# receiver_shield.net
KiCad netlist of a schematic drawn in EAGLE
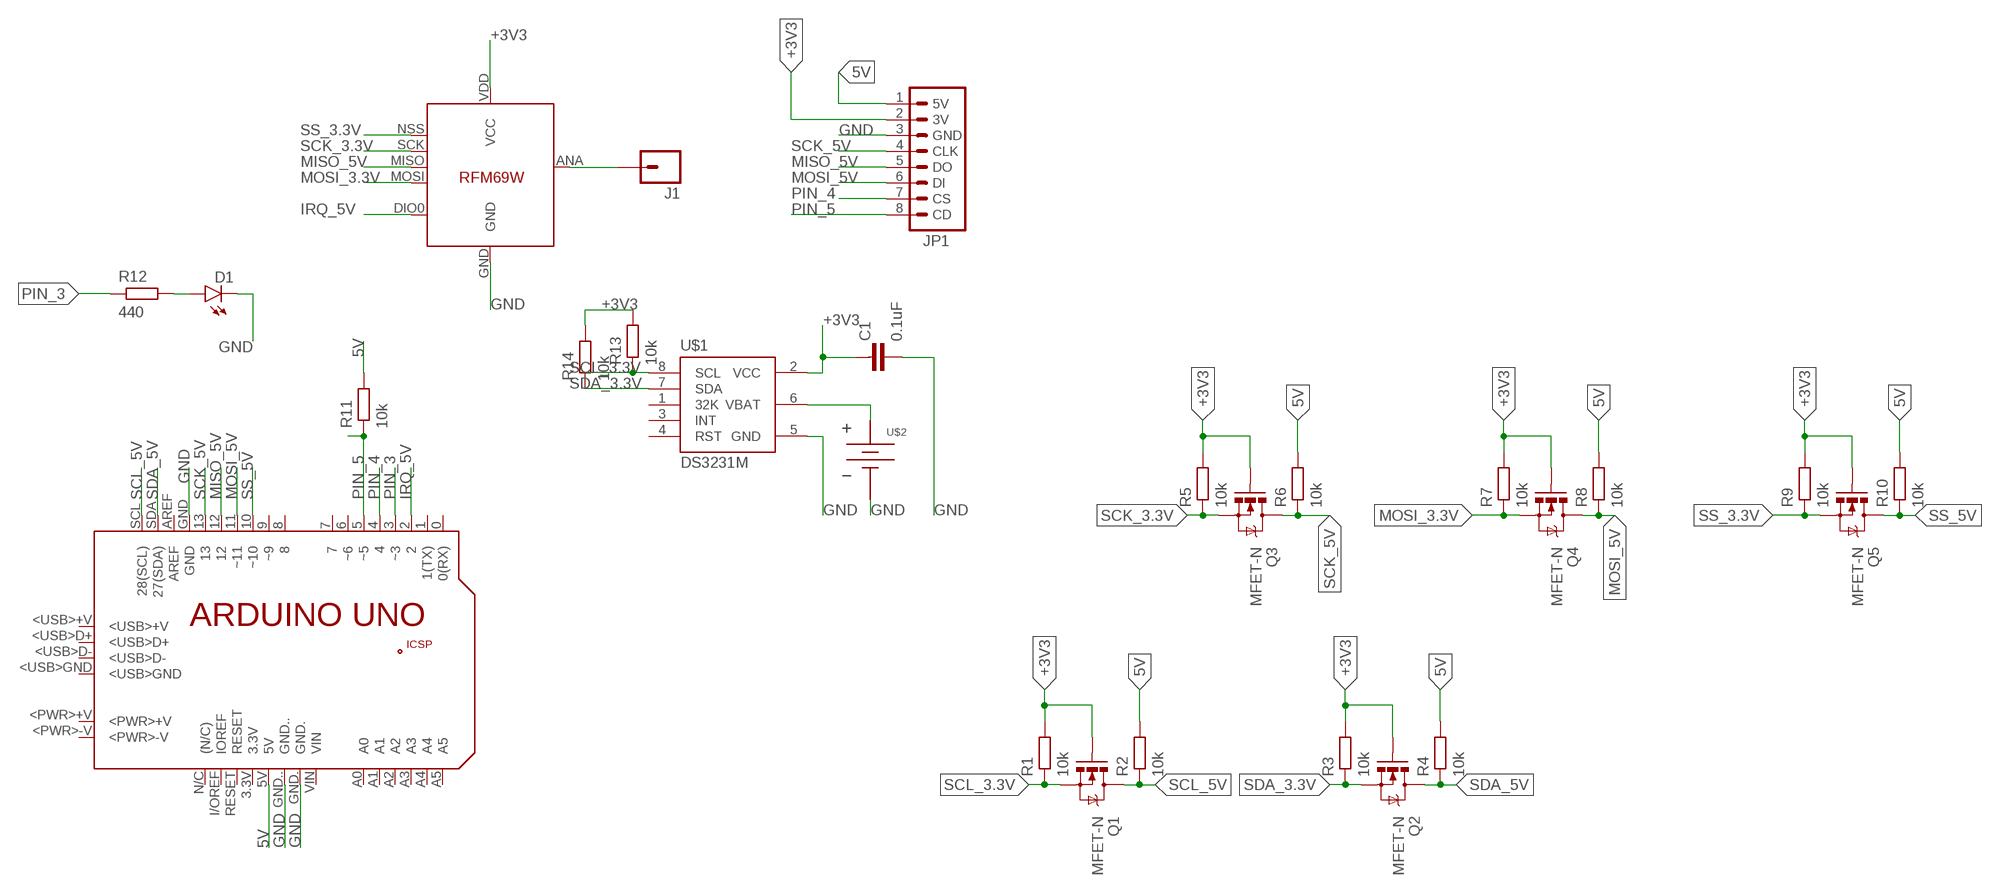
[diagram p0: schematic, sheet 1]

(export (version "E")
  (design (tool "Eeschema 10.0.6"))
  (components
    (comp (ref "C1")
      (value "0.1uF")
      (footprint "eagle-import:C0603-N")
      (libsource (lib "eagle-import") (part "CAPACITOR0603-N"))
    )
    (comp (ref "D1")
      (value "LED0603")
      (footprint "eagle-import:LED-0603")
      (libsource (lib "eagle-import") (part "LED0603"))
    )
    (comp (ref "J1")
      (value "M01NOSILK-KIT")
      (footprint "eagle-import:1X01NS-KIT")
      (libsource (lib "eagle-import") (part "M01NOSILK-KIT"))
    )
    (comp (ref "JP1")
      (value "SDCARD_BREAKOUT_HEADER1X08")
      (footprint "eagle-import:SD_HEADER")
      (libsource (lib "eagle-import") (part "SDCARD_BREAKOUT_HEADER1X08"))
    )
    (comp (ref "PCB1")
      (value "ARDUINO_UNO")
      (footprint "eagle-import:ARDUINO_UNO")
      (libsource (lib "eagle-import") (part "ARDUINO_UNO"))
    )
    (comp (ref "Q1")
      (value "MFET-N")
      (footprint "eagle-import:SOT23-3")
      (libsource (lib "eagle-import") (part "MOSFET-NCHANNELAO3404A"))
    )
    (comp (ref "Q2")
      (value "MFET-N")
      (footprint "eagle-import:SOT23-3")
      (libsource (lib "eagle-import") (part "MOSFET-NCHANNELAO3404A"))
    )
    (comp (ref "Q3")
      (value "MFET-N")
      (footprint "eagle-import:SOT23-3")
      (libsource (lib "eagle-import") (part "MOSFET-NCHANNELAO3404A"))
    )
    (comp (ref "Q4")
      (value "MFET-N")
      (footprint "eagle-import:SOT23-3")
      (libsource (lib "eagle-import") (part "MOSFET-NCHANNELAO3404A"))
    )
    (comp (ref "Q5")
      (value "MFET-N")
      (footprint "eagle-import:SOT23-3")
      (libsource (lib "eagle-import") (part "MOSFET-NCHANNELAO3404A"))
    )
    (comp (ref "R1")
      (value "10k")
      (footprint "eagle-import:R0603-N")
      (libsource (lib "eagle-import") (part "RESISTOR0603-N"))
    )
    (comp (ref "R2")
      (value "10k")
      (footprint "eagle-import:R0603-N")
      (libsource (lib "eagle-import") (part "RESISTOR0603-N"))
    )
    (comp (ref "R3")
      (value "10k")
      (footprint "eagle-import:R0603-N")
      (libsource (lib "eagle-import") (part "RESISTOR0603-N"))
    )
    (comp (ref "R4")
      (value "10k")
      (footprint "eagle-import:R0603-N")
      (libsource (lib "eagle-import") (part "RESISTOR0603-N"))
    )
    (comp (ref "R5")
      (value "10k")
      (footprint "eagle-import:R0603-N")
      (libsource (lib "eagle-import") (part "RESISTOR0603-N"))
    )
    (comp (ref "R6")
      (value "10k")
      (footprint "eagle-import:R0603-N")
      (libsource (lib "eagle-import") (part "RESISTOR0603-N"))
    )
    (comp (ref "R7")
      (value "10k")
      (footprint "eagle-import:R0603-N")
      (libsource (lib "eagle-import") (part "RESISTOR0603-N"))
    )
    (comp (ref "R8")
      (value "10k")
      (footprint "eagle-import:R0603-N")
      (libsource (lib "eagle-import") (part "RESISTOR0603-N"))
    )
    (comp (ref "R9")
      (value "10k")
      (footprint "eagle-import:R0603-N")
      (libsource (lib "eagle-import") (part "RESISTOR0603-N"))
    )
    (comp (ref "R10")
      (value "10k")
      (footprint "eagle-import:R0603-N")
      (libsource (lib "eagle-import") (part "RESISTOR0603-N"))
    )
    (comp (ref "R11")
      (value "10k")
      (footprint "eagle-import:R0603-N")
      (libsource (lib "eagle-import") (part "RESISTOR0603-N"))
    )
    (comp (ref "R12")
      (value "440")
      (footprint "eagle-import:R0603-N")
      (libsource (lib "eagle-import") (part "RESISTOR0603-N"))
    )
    (comp (ref "R13")
      (value "10k")
      (footprint "eagle-import:R0603-N")
      (libsource (lib "eagle-import") (part "RESISTOR0603-N"))
    )
    (comp (ref "R14")
      (value "10k")
      (footprint "eagle-import:R0603-N")
      (libsource (lib "eagle-import") (part "RESISTOR0603-N"))
    )
    (comp (ref "U$1")
      (value "DS3231M")
      (footprint "eagle-import:SO08")
      (libsource (lib "eagle-import") (part "DS3231M"))
    )
    (comp (ref "U$2")
      (value "2032_BAT_HLDR")
      (footprint "eagle-import:2032_BAT_HLDR_MPD")
      (libsource (lib "eagle-import") (part "2032_BAT_HLDR"))
    )
    (comp (ref "U$4")
      (value "RFM69")
      (footprint "eagle-import:RFM69W-MINPADS")
      (libsource (lib "eagle-import") (part "RFM69"))
    )
  )
  (nets
    (net (code "1") (name "+3V3") (class "Default")
      (node (ref "C1") (pin "1") (pinfunction "1_1") (pintype "passive"))
      (node (ref "JP1") (pin "2") (pinfunction "3V_2") (pintype "passive"))
      (node (ref "Q1") (pin "1") (pinfunction "G_1") (pintype "passive"))
      (node (ref "Q2") (pin "1") (pinfunction "G_1") (pintype "passive"))
      (node (ref "Q3") (pin "1") (pinfunction "G_1") (pintype "passive"))
      (node (ref "Q4") (pin "1") (pinfunction "G_1") (pintype "passive"))
      (node (ref "Q5") (pin "1") (pinfunction "G_1") (pintype "passive"))
      (node (ref "R1") (pin "2") (pinfunction "P$2_2") (pintype "passive"))
      (node (ref "R13") (pin "2") (pinfunction "P$2_2") (pintype "passive"))
      (node (ref "R14") (pin "2") (pinfunction "P$2_2") (pintype "passive"))
      (node (ref "R3") (pin "2") (pinfunction "P$2_2") (pintype "passive"))
      (node (ref "R5") (pin "2") (pinfunction "P$2_2") (pintype "passive"))
      (node (ref "R7") (pin "2") (pinfunction "P$2_2") (pintype "passive"))
      (node (ref "R9") (pin "2") (pinfunction "P$2_2") (pintype "passive"))
      (node (ref "U$1") (pin "2") (pinfunction "VCC_2") (pintype "power_in"))
      (node (ref "U$4") (pin "VDD") (pinfunction "VCC_VDD") (pintype "power_in"))
    )
    (net (code "2") (name "/GND") (class "Default")
      (node (ref "C1") (pin "2") (pinfunction "2_2") (pintype "passive"))
      (node (ref "D1") (pin "C") (pinfunction "C_C") (pintype "passive"))
      (node (ref "JP1") (pin "3") (pinfunction "GND_3") (pintype "passive"))
      (node (ref "PCB1") (pin "GND") (pinfunction "GND_GND") (pintype "bidirectional"))
      (node (ref "PCB1") (pin "GND.") (pinfunction "GND._GND.") (pintype "bidirectional"))
      (node (ref "PCB1") (pin "GND..") (pinfunction "GND.._GND..") (pintype "bidirectional"))
      (node (ref "U$1") (pin "5") (pinfunction "GND_5") (pintype "power_in"))
      (node (ref "U$2") (pin "P$1") (pinfunction "GND_P$1") (pintype "bidirectional"))
      (node (ref "U$4") (pin "GND") (pinfunction "GND_GND") (pintype "power_in"))
    )
    (net (code "3") (name "/IRQ_5V") (class "Default")
      (node (ref "PCB1") (pin "2") (pinfunction "2_2") (pintype "bidirectional"))
      (node (ref "U$4") (pin "DIO0") (pinfunction "DIO0_DIO0") (pintype "open_collector"))
    )
    (net (code "4") (name "/MISO_5V") (class "Default")
      (node (ref "JP1") (pin "5") (pinfunction "DO_5") (pintype "passive"))
      (node (ref "PCB1") (pin "12") (pinfunction "12_12") (pintype "bidirectional"))
      (node (ref "U$4") (pin "MISO") (pinfunction "MISO_MISO") (pintype "input"))
    )
    (net (code "5") (name "/PIN_4") (class "Default")
      (node (ref "JP1") (pin "7") (pinfunction "CS_7") (pintype "passive"))
      (node (ref "PCB1") (pin "4") (pinfunction "4_4") (pintype "bidirectional"))
    )
    (net (code "6") (name "/PIN_5") (class "Default")
      (node (ref "JP1") (pin "8") (pinfunction "CD_8") (pintype "passive"))
      (node (ref "PCB1") (pin "5") (pinfunction "~{5}_5") (pintype "bidirectional"))
      (node (ref "R11") (pin "1") (pinfunction "P$1_1") (pintype "passive"))
    )
    (net (code "7") (name "5V") (class "Default")
      (node (ref "JP1") (pin "1") (pinfunction "5V_1") (pintype "passive"))
      (node (ref "PCB1") (pin "5V") (pinfunction "5V_5V") (pintype "bidirectional"))
      (node (ref "R10") (pin "2") (pinfunction "P$2_2") (pintype "passive"))
      (node (ref "R11") (pin "2") (pinfunction "P$2_2") (pintype "passive"))
      (node (ref "R2") (pin "2") (pinfunction "P$2_2") (pintype "passive"))
      (node (ref "R4") (pin "2") (pinfunction "P$2_2") (pintype "passive"))
      (node (ref "R6") (pin "2") (pinfunction "P$2_2") (pintype "passive"))
      (node (ref "R8") (pin "2") (pinfunction "P$2_2") (pintype "passive"))
    )
    (net (code "8") (name "MOSI_3.3V") (class "Default")
      (node (ref "Q4") (pin "2") (pinfunction "S_2") (pintype "passive"))
      (node (ref "R7") (pin "1") (pinfunction "P$1_1") (pintype "passive"))
      (node (ref "U$4") (pin "MOSI") (pinfunction "MOSI_MOSI") (pintype "output"))
    )
    (net (code "9") (name "MOSI_5V") (class "Default")
      (node (ref "JP1") (pin "6") (pinfunction "DI_6") (pintype "passive"))
      (node (ref "PCB1") (pin "11") (pinfunction "~{11}_11") (pintype "bidirectional"))
      (node (ref "Q4") (pin "3") (pinfunction "D_3") (pintype "passive"))
      (node (ref "R8") (pin "1") (pinfunction "P$1_1") (pintype "passive"))
    )
    (net (code "10") (name "Net-(R12-P$2)") (class "Default")
      (node (ref "D1") (pin "A") (pinfunction "A_A") (pintype "passive"))
      (node (ref "R12") (pin "2") (pinfunction "P$2_2") (pintype "passive"))
    )
    (net (code "11") (name "Net-(U$1-VBAT)") (class "Default")
      (node (ref "U$1") (pin "6") (pinfunction "VBAT_6") (pintype "power_in"))
      (node (ref "U$2") (pin "P$2") (pinfunction "VBAT_P$2") (pintype "bidirectional"))
    )
    (net (code "12") (name "Net-(U$4-ANT)") (class "Default")
      (node (ref "J1") (pin "1") (pinfunction "1_1") (pintype "passive"))
      (node (ref "U$4") (pin "ANA") (pinfunction "ANT_ANA") (pintype "passive"))
    )
    (net (code "13") (name "PIN_3") (class "Default")
      (node (ref "PCB1") (pin "3") (pinfunction "~{3}_3") (pintype "bidirectional"))
      (node (ref "R12") (pin "1") (pinfunction "P$1_1") (pintype "passive"))
    )
    (net (code "14") (name "SCK_3.3V") (class "Default")
      (node (ref "Q3") (pin "2") (pinfunction "S_2") (pintype "passive"))
      (node (ref "R5") (pin "1") (pinfunction "P$1_1") (pintype "passive"))
      (node (ref "U$4") (pin "SCK") (pinfunction "SCK_SCK") (pintype "input"))
    )
    (net (code "15") (name "SCK_5V") (class "Default")
      (node (ref "JP1") (pin "4") (pinfunction "CLK_4") (pintype "passive"))
      (node (ref "PCB1") (pin "13") (pinfunction "13_13") (pintype "bidirectional"))
      (node (ref "Q3") (pin "3") (pinfunction "D_3") (pintype "passive"))
      (node (ref "R6") (pin "1") (pinfunction "P$1_1") (pintype "passive"))
    )
    (net (code "16") (name "SCL_3.3V") (class "Default")
      (node (ref "Q1") (pin "2") (pinfunction "S_2") (pintype "passive"))
      (node (ref "R1") (pin "1") (pinfunction "P$1_1") (pintype "passive"))
      (node (ref "R13") (pin "1") (pinfunction "P$1_1") (pintype "passive"))
      (node (ref "U$1") (pin "8") (pinfunction "SCL_8") (pintype "bidirectional"))
    )
    (net (code "17") (name "SCL_5V") (class "Default")
      (node (ref "PCB1") (pin "SCL") (pinfunction "28(SCL)_SCL") (pintype "bidirectional"))
      (node (ref "Q1") (pin "3") (pinfunction "D_3") (pintype "passive"))
      (node (ref "R2") (pin "1") (pinfunction "P$1_1") (pintype "passive"))
    )
    (net (code "18") (name "SDA_3.3V") (class "Default")
      (node (ref "Q2") (pin "2") (pinfunction "S_2") (pintype "passive"))
      (node (ref "R14") (pin "1") (pinfunction "P$1_1") (pintype "passive"))
      (node (ref "R3") (pin "1") (pinfunction "P$1_1") (pintype "passive"))
      (node (ref "U$1") (pin "7") (pinfunction "SDA_7") (pintype "bidirectional"))
    )
    (net (code "19") (name "SDA_5V") (class "Default")
      (node (ref "PCB1") (pin "SDA") (pinfunction "27(SDA)_SDA") (pintype "bidirectional"))
      (node (ref "Q2") (pin "3") (pinfunction "D_3") (pintype "passive"))
      (node (ref "R4") (pin "1") (pinfunction "P$1_1") (pintype "passive"))
    )
    (net (code "20") (name "SS_3.3V") (class "Default")
      (node (ref "Q5") (pin "2") (pinfunction "S_2") (pintype "passive"))
      (node (ref "R9") (pin "1") (pinfunction "P$1_1") (pintype "passive"))
      (node (ref "U$4") (pin "NSS") (pinfunction "SEL_NSS") (pintype "input"))
    )
    (net (code "21") (name "SS_5V") (class "Default")
      (node (ref "PCB1") (pin "10") (pinfunction "~{10}_10") (pintype "bidirectional"))
      (node (ref "Q5") (pin "3") (pinfunction "D_3") (pintype "passive"))
      (node (ref "R10") (pin "1") (pinfunction "P$1_1") (pintype "passive"))
    )
    (net (code "22") (name "unconnected-(PCB1-(N{slash}C)-PadN{slash}C)") (class "Default")
      (node (ref "PCB1") (pin "N/C") (pinfunction "(N/C)_N/C") (pintype "bidirectional"))
    )
    (net (code "23") (name "unconnected-(PCB1-0(RX)-Pad0)") (class "Default")
      (node (ref "PCB1") (pin "0") (pinfunction "0(RX)_0") (pintype "bidirectional"))
    )
    (net (code "24") (name "unconnected-(PCB1-1(TX)-Pad1)") (class "Default")
      (node (ref "PCB1") (pin "1") (pinfunction "1(TX)_1") (pintype "bidirectional"))
    )
    (net (code "25") (name "unconnected-(PCB1-IOREF-PadI{slash}OREF)") (class "Default")
      (node (ref "PCB1") (pin "I/OREF") (pinfunction "IOREF_I/OREF") (pintype "bidirectional"))
    )
    (net (code "26") (name "unconnected-(PCB1-Pad+5V)") (class "Default")
      (node (ref "PCB1") (pin "+5V") (pinfunction "+5V_+5V") (pintype "bidirectional"))
    )
    (net (code "27") (name "unconnected-(PCB1-Pad3.3V)") (class "Default")
      (node (ref "PCB1") (pin "3.3V") (pinfunction "3.3V_3.3V") (pintype "bidirectional"))
    )
    (net (code "28") (name "unconnected-(PCB1-Pad7)") (class "Default")
      (node (ref "PCB1") (pin "7") (pinfunction "7_7") (pintype "bidirectional"))
    )
    (net (code "29") (name "unconnected-(PCB1-Pad8)") (class "Default")
      (node (ref "PCB1") (pin "8") (pinfunction "8_8") (pintype "bidirectional"))
    )
    (net (code "30") (name "unconnected-(PCB1-Pad<PWR>+V)") (class "Default")
      (node (ref "PCB1") (pin "<PWR>+V") (pinfunction "<PWR>+V_<PWR>+V") (pintype "bidirectional"))
    )
    (net (code "31") (name "unconnected-(PCB1-Pad<PWR>-V)") (class "Default")
      (node (ref "PCB1") (pin "<PWR>-V") (pinfunction "<PWR>-V_<PWR>-V") (pintype "bidirectional"))
    )
    (net (code "32") (name "unconnected-(PCB1-Pad<USB>+V)") (class "Default")
      (node (ref "PCB1") (pin "<USB>+V") (pinfunction "<USB>+V_<USB>+V") (pintype "bidirectional"))
    )
    (net (code "33") (name "unconnected-(PCB1-Pad<USB>D+)") (class "Default")
      (node (ref "PCB1") (pin "<USB>D+") (pinfunction "<USB>D+_<USB>D+") (pintype "bidirectional"))
    )
    (net (code "34") (name "unconnected-(PCB1-Pad<USB>D-)") (class "Default")
      (node (ref "PCB1") (pin "<USB>D-") (pinfunction "<USB>D-_<USB>D-") (pintype "bidirectional"))
    )
    (net (code "35") (name "unconnected-(PCB1-Pad<USB>GND)") (class "Default")
      (node (ref "PCB1") (pin "<USB>GND") (pinfunction "<USB>GND_<USB>GND") (pintype "bidirectional"))
    )
    (net (code "36") (name "unconnected-(PCB1-PadA0)") (class "Default")
      (node (ref "PCB1") (pin "A0") (pinfunction "A0_A0") (pintype "bidirectional"))
    )
    (net (code "37") (name "unconnected-(PCB1-PadA1)") (class "Default")
      (node (ref "PCB1") (pin "A1") (pinfunction "A1_A1") (pintype "bidirectional"))
    )
    (net (code "38") (name "unconnected-(PCB1-PadA2)") (class "Default")
      (node (ref "PCB1") (pin "A2") (pinfunction "A2_A2") (pintype "bidirectional"))
    )
    (net (code "39") (name "unconnected-(PCB1-PadA3)") (class "Default")
      (node (ref "PCB1") (pin "A3") (pinfunction "A3_A3") (pintype "bidirectional"))
    )
    (net (code "40") (name "unconnected-(PCB1-PadA4)") (class "Default")
      (node (ref "PCB1") (pin "A4") (pinfunction "A4_A4") (pintype "bidirectional"))
    )
    (net (code "41") (name "unconnected-(PCB1-PadA5)") (class "Default")
      (node (ref "PCB1") (pin "A5") (pinfunction "A5_A5") (pintype "bidirectional"))
    )
    (net (code "42") (name "unconnected-(PCB1-PadAREF)") (class "Default")
      (node (ref "PCB1") (pin "AREF") (pinfunction "AREF_AREF") (pintype "bidirectional"))
    )
    (net (code "43") (name "unconnected-(PCB1-PadGND_)") (class "Default")
      (node (ref "PCB1") (pin "GND_") (pinfunction "GND__GND_") (pintype "bidirectional"))
    )
    (net (code "44") (name "unconnected-(PCB1-PadMISO)") (class "Default")
      (node (ref "PCB1") (pin "MISO") (pinfunction "MISO_MISO") (pintype "bidirectional"))
    )
    (net (code "45") (name "unconnected-(PCB1-PadMOSI)") (class "Default")
      (node (ref "PCB1") (pin "MOSI") (pinfunction "MOSI_MOSI") (pintype "bidirectional"))
    )
    (net (code "46") (name "unconnected-(PCB1-PadRESET)") (class "Default")
      (node (ref "PCB1") (pin "RESET") (pinfunction "RESET_RESET") (pintype "bidirectional"))
    )
    (net (code "47") (name "unconnected-(PCB1-PadRESET.)") (class "Default")
      (node (ref "PCB1") (pin "RESET.") (pinfunction "RESET._RESET.") (pintype "bidirectional"))
    )
    (net (code "48") (name "unconnected-(PCB1-PadSCK)") (class "Default")
      (node (ref "PCB1") (pin "SCK") (pinfunction "SCK_SCK") (pintype "bidirectional"))
    )
    (net (code "49") (name "unconnected-(PCB1-PadVIN)") (class "Default")
      (node (ref "PCB1") (pin "VIN") (pinfunction "VIN_VIN") (pintype "bidirectional"))
    )
    (net (code "50") (name "unconnected-(PCB1-~{6}-Pad6)") (class "Default")
      (node (ref "PCB1") (pin "6") (pinfunction "~{6}_6") (pintype "bidirectional"))
    )
    (net (code "51") (name "unconnected-(PCB1-~{9}-Pad9)") (class "Default")
      (node (ref "PCB1") (pin "9") (pinfunction "~{9}_9") (pintype "bidirectional"))
    )
    (net (code "52") (name "unconnected-(U$1-32K-Pad1)") (class "Default")
      (node (ref "U$1") (pin "1") (pinfunction "32K_1") (pintype "bidirectional"))
    )
    (net (code "53") (name "unconnected-(U$1-INT-Pad3)") (class "Default")
      (node (ref "U$1") (pin "3") (pinfunction "INT_3") (pintype "bidirectional"))
    )
    (net (code "54") (name "unconnected-(U$1-RST-Pad4)") (class "Default")
      (node (ref "U$1") (pin "4") (pinfunction "RST_4") (pintype "bidirectional"))
    )
  )
)
